# design.net
KiCad netlist of a schematic drawn in Altium Designer
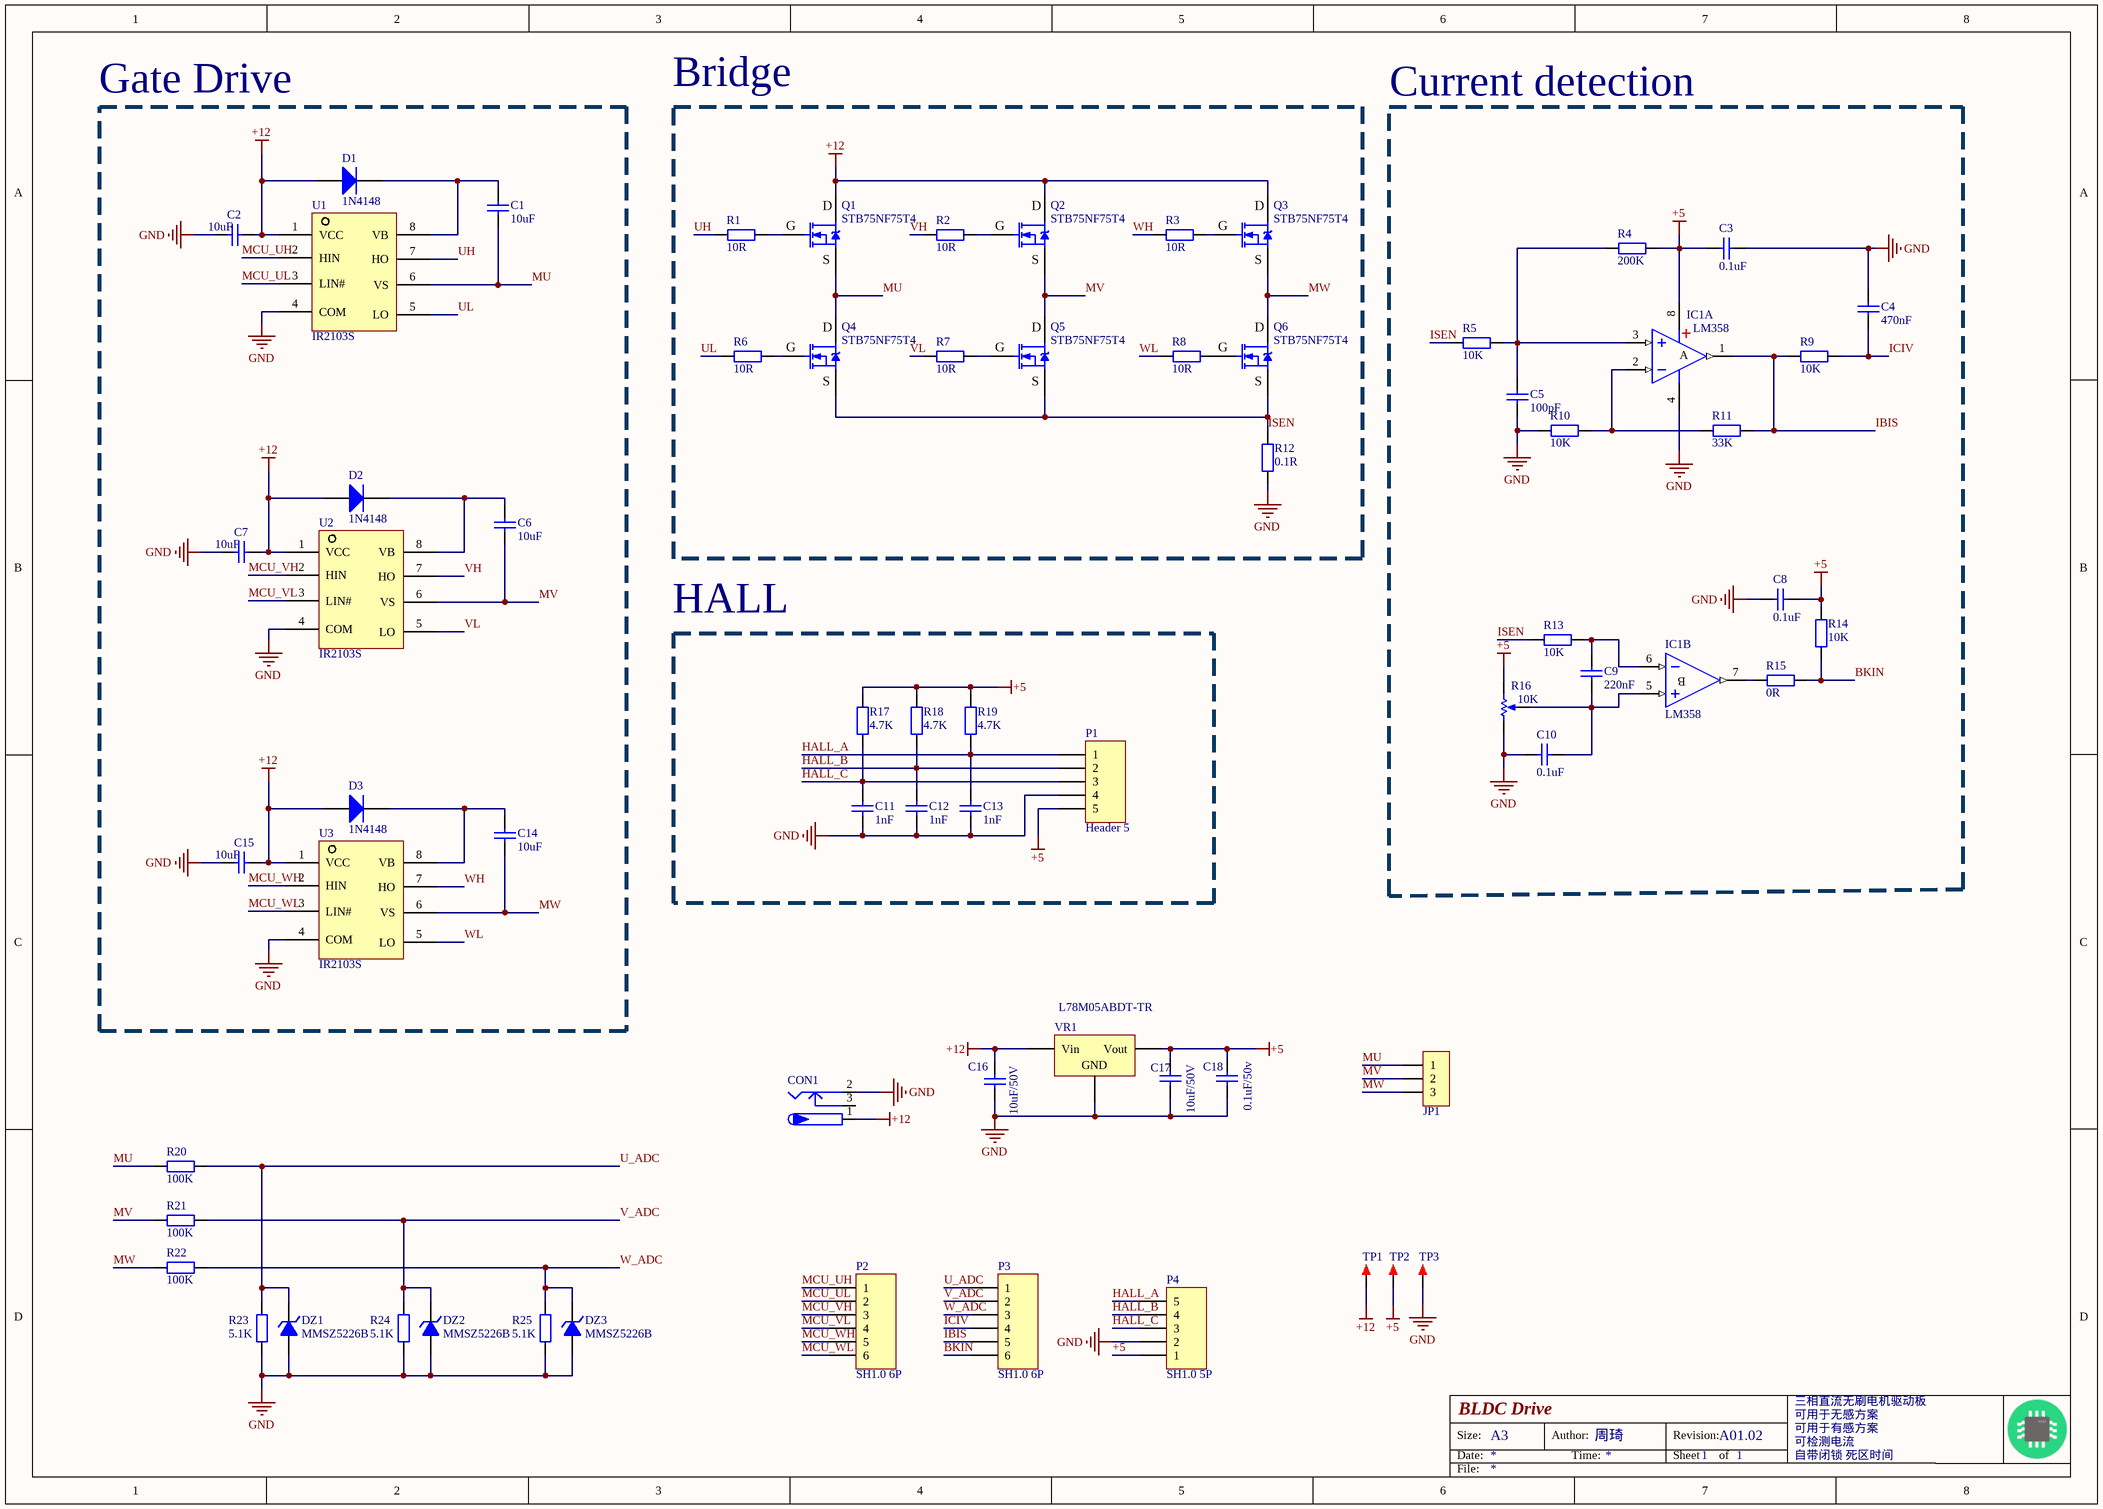
[diagram p0: 原理图.SchDoc]

(export (version "E")
  (design (tool "Eeschema 10.0.6"))
  (components
    (comp (ref "C1")
      (value "10uF")
      (footprint "C0603_L")
      (description "贴片电容")
      (libsource (lib "0.1 - 电阻-电容-电感-磁珠-电位器") (part "C"))
    )
    (comp (ref "C2")
      (value "10uF")
      (footprint "C0603_L")
      (description "贴片电容")
      (libsource (lib "0.1 - 电阻-电容-电感-磁珠-电位器") (part "C"))
    )
    (comp (ref "C3")
      (value "0.1uF")
      (footprint "C0603_L")
      (description "贴片电容")
      (libsource (lib "0.1 - 电阻-电容-电感-磁珠-电位器") (part "C"))
    )
    (comp (ref "C4")
      (value "470nF")
      (footprint "C0603_L")
      (description "贴片电容")
      (libsource (lib "0.1 - 电阻-电容-电感-磁珠-电位器") (part "C"))
    )
    (comp (ref "C5")
      (value "100pF")
      (footprint "C0603_L")
      (description "贴片电容")
      (libsource (lib "0.1 - 电阻-电容-电感-磁珠-电位器") (part "C"))
    )
    (comp (ref "C6")
      (value "10uF")
      (footprint "C0603_L")
      (description "贴片电容")
      (libsource (lib "0.1 - 电阻-电容-电感-磁珠-电位器") (part "C"))
    )
    (comp (ref "C7")
      (value "10uF")
      (footprint "C0603_L")
      (description "贴片电容")
      (libsource (lib "0.1 - 电阻-电容-电感-磁珠-电位器") (part "C"))
    )
    (comp (ref "C8")
      (value "0.1uF")
      (footprint "C0603_L")
      (description "贴片电容")
      (libsource (lib "0.1 - 电阻-电容-电感-磁珠-电位器") (part "C"))
    )
    (comp (ref "C9")
      (value "220nF")
      (footprint "C0603_L")
      (description "贴片电容")
      (libsource (lib "0.1 - 电阻-电容-电感-磁珠-电位器") (part "C"))
    )
    (comp (ref "C10")
      (value "0.1uF")
      (footprint "C0603_L")
      (description "贴片电容")
      (libsource (lib "0.1 - 电阻-电容-电感-磁珠-电位器") (part "C"))
    )
    (comp (ref "C11")
      (value "1nF")
      (footprint "C0603_L")
      (description "贴片电容")
      (libsource (lib "0.1 - 电阻-电容-电感-磁珠-电位器") (part "C"))
    )
    (comp (ref "C12")
      (value "1nF")
      (footprint "C0603_L")
      (description "贴片电容")
      (libsource (lib "0.1 - 电阻-电容-电感-磁珠-电位器") (part "C"))
    )
    (comp (ref "C13")
      (value "1nF")
      (footprint "C0603_L")
      (description "贴片电容")
      (libsource (lib "0.1 - 电阻-电容-电感-磁珠-电位器") (part "C"))
    )
    (comp (ref "C14")
      (value "10uF")
      (footprint "C0603_L")
      (description "贴片电容")
      (libsource (lib "0.1 - 电阻-电容-电感-磁珠-电位器") (part "C"))
    )
    (comp (ref "C15")
      (value "10uF")
      (footprint "C0603_L")
      (description "贴片电容")
      (libsource (lib "0.1 - 电阻-电容-电感-磁珠-电位器") (part "C"))
    )
    (comp (ref "C16")
      (value "10uF/50V")
      (footprint "C1206_L")
      (description "C89632")
      (libsource (lib "Miscellaneous Devices") (part "Cap"))
    )
    (comp (ref "C17")
      (value "10uF/50V")
      (footprint "C1206_L")
      (description "C89632")
      (libsource (lib "Miscellaneous Devices") (part "Cap"))
    )
    (comp (ref "C18")
      (value "0.1uF/50v")
      (footprint "C0603_L")
      (libsource (lib "Miscellaneous Devices") (part "Cap"))
    )
    (comp (ref "CON1")
      (value "3.5*1.3")
      (footprint "DC-005")
      (description "低压电源接口")
      (libsource (lib "0.8 - 以太网-音频-Type-C USB插座") (part "P-DC"))
    )
    (comp (ref "D1")
      (value "1N4148")
      (footprint "SOD-123")
      (description "二极管")
      (libsource (lib "Miscellaneous Devices LC") (part "SOD-323 1N4148WS T4"))
    )
    (comp (ref "D2")
      (value "1N4148")
      (footprint "SOD-123")
      (description "二极管")
      (libsource (lib "Miscellaneous Devices LC") (part "SOD-323 1N4148WS T4"))
    )
    (comp (ref "D3")
      (value "1N4148")
      (footprint "SOD-123")
      (description "二极管")
      (libsource (lib "Miscellaneous Devices LC") (part "SOD-323 1N4148WS T4"))
    )
    (comp (ref "DZ1")
      (value "MMSZ5226B")
      (footprint "SOD-123")
      (description "3V/0.5W稳压管")
      (libsource (lib "0.2 - 二极管-TVS-ESD-整流桥") (part "1N4619"))
    )
    (comp (ref "DZ2")
      (value "MMSZ5226B")
      (footprint "SOD-123")
      (description "3V/0.5W稳压管")
      (libsource (lib "0.2 - 二极管-TVS-ESD-整流桥") (part "1N4619"))
    )
    (comp (ref "DZ3")
      (value "MMSZ5226B")
      (footprint "SOD-123")
      (description "3V/0.5W稳压管")
      (libsource (lib "0.2 - 二极管-TVS-ESD-整流桥") (part "1N4619"))
    )
    (comp (ref "IC1")
      (value "LM358")
      (footprint "SOP8_N")
      (description "双路运放")
      (libsource (lib "1.0 - 常见芯片") (part "LM358"))
    )
    (comp (ref "JP1")
      (value "HDR-1X3")
      (footprint "KF350-3P")
      (description "3P接插件")
      (fields (field (name "版权归属") "源创客"))
      (libsource (lib "接插件") (part "Header 3"))
    )
    (comp (ref "P1")
      (value "Header 5")
      (footprint "SH 1.0-LS-5P")
      (description "Header, 5-Pin")
      (fields (field (name "PUBLISHER") "Altium Limited"))
      (libsource (lib "") (part "Header 5_1"))
    )
    (comp (ref "P2")
      (value "SH1.0 6P")
      (footprint "SH 1.0-WS-6P")
      (description "Header, 6-Pin")
      (fields (field (name "PUBLISHER") "Altium Limited"))
      (libsource (lib "Miscellaneous Connectors") (part "Header 6"))
    )
    (comp (ref "P3")
      (value "SH1.0 6P")
      (footprint "SH 1.0-WS-6P")
      (description "Header, 6-Pin")
      (fields (field (name "PUBLISHER") "Altium Limited"))
      (libsource (lib "Miscellaneous Connectors") (part "Header 6"))
    )
    (comp (ref "P4")
      (value "SH1.0 5P")
      (footprint "SH 1.0-LS-5P")
      (description "Header, 5-Pin")
      (fields (field (name "PUBLISHER") "Altium Limited"))
      (libsource (lib "Miscellaneous Connectors") (part "Header 5"))
    )
    (comp (ref "Q1")
      (value "STB75NF75T4")
      (footprint "TO252")
      (description "N沟道 55V/17A")
      (libsource (lib "0.4 - 三极管-场效应管-可控硅") (part "IRFR024NTRPBF"))
    )
    (comp (ref "Q2")
      (value "STB75NF75T4")
      (footprint "TO252")
      (description "N沟道 55V/17A")
      (libsource (lib "0.4 - 三极管-场效应管-可控硅") (part "IRFR024NTRPBF"))
    )
    (comp (ref "Q3")
      (value "STB75NF75T4")
      (footprint "TO252")
      (description "N沟道 55V/17A")
      (libsource (lib "0.4 - 三极管-场效应管-可控硅") (part "IRFR024NTRPBF"))
    )
    (comp (ref "Q4")
      (value "STB75NF75T4")
      (footprint "TO252")
      (description "N沟道 55V/17A")
      (libsource (lib "0.4 - 三极管-场效应管-可控硅") (part "IRFR024NTRPBF"))
    )
    (comp (ref "Q5")
      (value "STB75NF75T4")
      (footprint "TO252")
      (description "N沟道 55V/17A")
      (libsource (lib "0.4 - 三极管-场效应管-可控硅") (part "IRFR024NTRPBF"))
    )
    (comp (ref "Q6")
      (value "STB75NF75T4")
      (footprint "TO252")
      (description "N沟道 55V/17A")
      (libsource (lib "0.4 - 三极管-场效应管-可控硅") (part "IRFR024NTRPBF"))
    )
    (comp (ref "R1")
      (value "10R")
      (footprint "R0603_L")
      (description "贴片电阻")
      (libsource (lib "0.1 - 电阻-电容-电感-磁珠-电位器") (part "R"))
    )
    (comp (ref "R2")
      (value "10R")
      (footprint "R0603_L")
      (description "贴片电阻")
      (libsource (lib "0.1 - 电阻-电容-电感-磁珠-电位器") (part "R"))
    )
    (comp (ref "R3")
      (value "10R")
      (footprint "R0603_L")
      (description "贴片电阻")
      (libsource (lib "0.1 - 电阻-电容-电感-磁珠-电位器") (part "R"))
    )
    (comp (ref "R4")
      (value "200K")
      (footprint "R0603_L")
      (description "贴片电阻")
      (libsource (lib "0.1 - 电阻-电容-电感-磁珠-电位器") (part "R"))
    )
    (comp (ref "R5")
      (value "10K")
      (footprint "R0603_L")
      (description "贴片电阻")
      (libsource (lib "0.1 - 电阻-电容-电感-磁珠-电位器") (part "R"))
    )
    (comp (ref "R6")
      (value "10R")
      (footprint "R0603_L")
      (description "贴片电阻")
      (libsource (lib "0.1 - 电阻-电容-电感-磁珠-电位器") (part "R"))
    )
    (comp (ref "R7")
      (value "10R")
      (footprint "R0603_L")
      (description "贴片电阻")
      (libsource (lib "0.1 - 电阻-电容-电感-磁珠-电位器") (part "R"))
    )
    (comp (ref "R8")
      (value "10R")
      (footprint "R0603_L")
      (description "贴片电阻")
      (libsource (lib "0.1 - 电阻-电容-电感-磁珠-电位器") (part "R"))
    )
    (comp (ref "R9")
      (value "10K")
      (footprint "R0603_L")
      (description "贴片电阻")
      (libsource (lib "0.1 - 电阻-电容-电感-磁珠-电位器") (part "R"))
    )
    (comp (ref "R10")
      (value "10K")
      (footprint "R0603_L")
      (description "贴片电阻")
      (libsource (lib "0.1 - 电阻-电容-电感-磁珠-电位器") (part "R"))
    )
    (comp (ref "R11")
      (value "33K")
      (footprint "R0603_L")
      (description "贴片电阻")
      (libsource (lib "0.1 - 电阻-电容-电感-磁珠-电位器") (part "R"))
    )
    (comp (ref "R12")
      (value "0.1R")
      (footprint "R2512_M")
      (description "贴片电阻")
      (libsource (lib "0.1 - 电阻-电容-电感-磁珠-电位器") (part "R"))
    )
    (comp (ref "R13")
      (value "10K")
      (footprint "R0603_L")
      (description "贴片电阻")
      (libsource (lib "0.1 - 电阻-电容-电感-磁珠-电位器") (part "R"))
    )
    (comp (ref "R14")
      (value "10K")
      (footprint "R0603_L")
      (description "贴片电阻")
      (libsource (lib "0.1 - 电阻-电容-电感-磁珠-电位器") (part "R"))
    )
    (comp (ref "R15")
      (value "0R")
      (footprint "R0603_L")
      (description "贴片电阻")
      (libsource (lib "0.1 - 电阻-电容-电感-磁珠-电位器") (part "R"))
    )
    (comp (ref "R16")
      (value "10K")
      (footprint "3303W")
      (description "Potentiometer")
      (fields (field (name "Comment") "RPot") (field (name "PUBLISHER") "Altium Limited"))
      (libsource (lib "Miscellaneous Devices") (part "RPot"))
    )
    (comp (ref "R17")
      (value "4.7K")
      (footprint "R0603_L")
      (description "贴片电阻")
      (libsource (lib "0.1 - 电阻-电容-电感-磁珠-电位器") (part "R"))
    )
    (comp (ref "R18")
      (value "4.7K")
      (footprint "R0603_L")
      (description "贴片电阻")
      (libsource (lib "0.1 - 电阻-电容-电感-磁珠-电位器") (part "R"))
    )
    (comp (ref "R19")
      (value "4.7K")
      (footprint "R0603_L")
      (description "贴片电阻")
      (libsource (lib "0.1 - 电阻-电容-电感-磁珠-电位器") (part "R"))
    )
    (comp (ref "R20")
      (value "100K")
      (footprint "R1206_L")
      (description "贴片电阻")
      (libsource (lib "0.1 - 电阻-电容-电感-磁珠-电位器") (part "R"))
    )
    (comp (ref "R21")
      (value "100K")
      (footprint "R1206_L")
      (description "贴片电阻")
      (libsource (lib "0.1 - 电阻-电容-电感-磁珠-电位器") (part "R"))
    )
    (comp (ref "R22")
      (value "100K")
      (footprint "R1206_L")
      (description "贴片电阻")
      (libsource (lib "0.1 - 电阻-电容-电感-磁珠-电位器") (part "R"))
    )
    (comp (ref "R23")
      (value "5.1K")
      (footprint "R0805_L")
      (description "贴片电阻")
      (libsource (lib "0.1 - 电阻-电容-电感-磁珠-电位器") (part "R"))
    )
    (comp (ref "R24")
      (value "5.1K")
      (footprint "R0805_L")
      (description "贴片电阻")
      (libsource (lib "0.1 - 电阻-电容-电感-磁珠-电位器") (part "R"))
    )
    (comp (ref "R25")
      (value "5.1K")
      (footprint "R0805_L")
      (description "贴片电阻")
      (libsource (lib "0.1 - 电阻-电容-电感-磁珠-电位器") (part "R"))
    )
    (comp (ref "TP1")
      (value "TEST")
      (footprint "TEST 1.6")
      (description "测试点")
      (libsource (lib "0.7 - 常用按键-开关-蜂鸣器-电池-测试点") (part "TEST"))
    )
    (comp (ref "TP2")
      (value "TEST")
      (footprint "TEST 1.6")
      (description "测试点")
      (libsource (lib "0.7 - 常用按键-开关-蜂鸣器-电池-测试点") (part "TEST"))
    )
    (comp (ref "TP3")
      (value "TEST")
      (footprint "TEST 1.6")
      (description "测试点")
      (libsource (lib "0.7 - 常用按键-开关-蜂鸣器-电池-测试点") (part "TEST"))
    )
    (comp (ref "U1")
      (value "IR2103S")
      (footprint "SOP8")
      (description "栅极驱动，SOP-8")
      (libsource (lib "Schlib1") (part "IR2103S"))
    )
    (comp (ref "U2")
      (value "IR2103S")
      (footprint "SOP8")
      (description "栅极驱动，SOP-8")
      (libsource (lib "Schlib1") (part "IR2103S"))
    )
    (comp (ref "U3")
      (value "IR2103S")
      (footprint "SOP8")
      (description "栅极驱动，SOP-8")
      (libsource (lib "Schlib1") (part "IR2103S"))
    )
    (comp (ref "VR1")
      (value "L78M05ABDT-TR")
      (footprint "TO-252")
      (description "低压差线性稳压(LDO)")
      (libsource (lib "LDO") (part "TO-252-2 L78M05ABDT-TR"))
    )
  )
  (nets
    (net (code "1") (name "+5") (class "Default")
      (node (ref "C17") (pin "2") (pinfunction "2_2") (pintype "passive"))
      (node (ref "C18") (pin "2") (pinfunction "2_2") (pintype "passive"))
      (node (ref "C3") (pin "1") (pinfunction "1_1") (pintype "passive"))
      (node (ref "C8") (pin "1") (pinfunction "1_1") (pintype "passive"))
      (node (ref "IC1") (pin "8") (pinfunction "V+_8") (pintype "power_in"))
      (node (ref "P1") (pin "5") (pinfunction "5_5") (pintype "passive"))
      (node (ref "P4") (pin "1") (pinfunction "1_1") (pintype "passive"))
      (node (ref "R14") (pin "1") (pinfunction "1_1") (pintype "passive"))
      (node (ref "R16") (pin "2") (pinfunction "BOT_2") (pintype "passive"))
      (node (ref "R17") (pin "2") (pinfunction "2_2") (pintype "passive"))
      (node (ref "R18") (pin "2") (pinfunction "2_2") (pintype "passive"))
      (node (ref "R19") (pin "2") (pinfunction "2_2") (pintype "passive"))
      (node (ref "R4") (pin "1") (pinfunction "1_1") (pintype "passive"))
      (node (ref "TP2") (pin "1") (pinfunction "1_1") (pintype "passive"))
      (node (ref "VR1") (pin "3") (pinfunction "Vout_3") (pintype "passive"))
    )
    (net (code "2") (name "+12") (class "Default")
      (node (ref "C15") (pin "2") (pinfunction "2_2") (pintype "passive"))
      (node (ref "C16") (pin "2") (pinfunction "2_2") (pintype "passive"))
      (node (ref "C2") (pin "2") (pinfunction "2_2") (pintype "passive"))
      (node (ref "C7") (pin "2") (pinfunction "2_2") (pintype "passive"))
      (node (ref "CON1") (pin "1") (pintype "power_in"))
      (node (ref "D1") (pin "1") (pinfunction "A_1") (pintype "passive"))
      (node (ref "D2") (pin "1") (pinfunction "A_1") (pintype "passive"))
      (node (ref "D3") (pin "1") (pinfunction "A_1") (pintype "passive"))
      (node (ref "Q1") (pin "2") (pinfunction "D_2") (pintype "passive"))
      (node (ref "Q2") (pin "2") (pinfunction "D_2") (pintype "passive"))
      (node (ref "Q3") (pin "2") (pinfunction "D_2") (pintype "passive"))
      (node (ref "TP1") (pin "1") (pinfunction "1_1") (pintype "passive"))
      (node (ref "U1") (pin "1") (pinfunction "VCC_1") (pintype "passive"))
      (node (ref "U2") (pin "1") (pinfunction "VCC_1") (pintype "passive"))
      (node (ref "U3") (pin "1") (pinfunction "VCC_1") (pintype "passive"))
      (node (ref "VR1") (pin "1") (pinfunction "Vin_1") (pintype "passive"))
    )
    (net (code "3") (name "/BKIN") (class "Default")
      (node (ref "P3") (pin "6") (pinfunction "6_6") (pintype "passive"))
      (node (ref "R14") (pin "2") (pinfunction "2_2") (pintype "passive"))
      (node (ref "R15") (pin "1") (pinfunction "1_1") (pintype "passive"))
    )
    (net (code "4") (name "/HALL_A") (class "Default")
      (node (ref "C13") (pin "2") (pinfunction "2_2") (pintype "passive"))
      (node (ref "P1") (pin "1") (pinfunction "1_1") (pintype "passive"))
      (node (ref "P4") (pin "5") (pinfunction "5_5") (pintype "passive"))
      (node (ref "R19") (pin "1") (pinfunction "1_1") (pintype "passive"))
    )
    (net (code "5") (name "/HALL_B") (class "Default")
      (node (ref "C12") (pin "2") (pinfunction "2_2") (pintype "passive"))
      (node (ref "P1") (pin "2") (pinfunction "2_2") (pintype "passive"))
      (node (ref "P4") (pin "4") (pinfunction "4_4") (pintype "passive"))
      (node (ref "R18") (pin "1") (pinfunction "1_1") (pintype "passive"))
    )
    (net (code "6") (name "/HALL_C") (class "Default")
      (node (ref "C11") (pin "2") (pinfunction "2_2") (pintype "passive"))
      (node (ref "P1") (pin "3") (pinfunction "3_3") (pintype "passive"))
      (node (ref "P4") (pin "3") (pinfunction "3_3") (pintype "passive"))
      (node (ref "R17") (pin "1") (pinfunction "1_1") (pintype "passive"))
    )
    (net (code "7") (name "/IBIS") (class "Default")
      (node (ref "IC1") (pin "1") (pinfunction "OUT_1") (pintype "output"))
      (node (ref "P3") (pin "5") (pinfunction "5_5") (pintype "passive"))
      (node (ref "R11") (pin "1") (pinfunction "1_1") (pintype "passive"))
      (node (ref "R9") (pin "2") (pinfunction "2_2") (pintype "passive"))
    )
    (net (code "8") (name "/ICIV") (class "Default")
      (node (ref "C4") (pin "2") (pinfunction "2_2") (pintype "passive"))
      (node (ref "P3") (pin "4") (pinfunction "4_4") (pintype "passive"))
      (node (ref "R9") (pin "1") (pinfunction "1_1") (pintype "passive"))
    )
    (net (code "9") (name "/ISEN") (class "Default")
      (node (ref "Q4") (pin "3") (pinfunction "S_3") (pintype "passive"))
      (node (ref "Q5") (pin "3") (pinfunction "S_3") (pintype "passive"))
      (node (ref "Q6") (pin "3") (pinfunction "S_3") (pintype "passive"))
      (node (ref "R12") (pin "2") (pinfunction "2_2") (pintype "passive"))
      (node (ref "R13") (pin "2") (pinfunction "2_2") (pintype "passive"))
      (node (ref "R5") (pin "2") (pinfunction "2_2") (pintype "passive"))
    )
    (net (code "10") (name "/MCU_UH") (class "Default")
      (node (ref "P2") (pin "1") (pinfunction "1_1") (pintype "passive"))
      (node (ref "U1") (pin "2") (pinfunction "HIN_2") (pintype "passive"))
    )
    (net (code "11") (name "/MCU_UL") (class "Default")
      (node (ref "P2") (pin "2") (pinfunction "2_2") (pintype "passive"))
      (node (ref "U1") (pin "3") (pinfunction "LIN#_3") (pintype "passive"))
    )
    (net (code "12") (name "/MCU_VH") (class "Default")
      (node (ref "P2") (pin "3") (pinfunction "3_3") (pintype "passive"))
      (node (ref "U2") (pin "2") (pinfunction "HIN_2") (pintype "passive"))
    )
    (net (code "13") (name "/MCU_VL") (class "Default")
      (node (ref "P2") (pin "4") (pinfunction "4_4") (pintype "passive"))
      (node (ref "U2") (pin "3") (pinfunction "LIN#_3") (pintype "passive"))
    )
    (net (code "14") (name "/MCU_WH") (class "Default")
      (node (ref "P2") (pin "5") (pinfunction "5_5") (pintype "passive"))
      (node (ref "U3") (pin "2") (pinfunction "HIN_2") (pintype "passive"))
    )
    (net (code "15") (name "/MCU_WL") (class "Default")
      (node (ref "P2") (pin "6") (pinfunction "6_6") (pintype "passive"))
      (node (ref "U3") (pin "3") (pinfunction "LIN#_3") (pintype "passive"))
    )
    (net (code "16") (name "/MU") (class "Default")
      (node (ref "C1") (pin "1") (pinfunction "1_1") (pintype "passive"))
      (node (ref "JP1") (pin "1") (pinfunction "1_1") (pintype "passive"))
      (node (ref "Q1") (pin "3") (pinfunction "S_3") (pintype "passive"))
      (node (ref "Q4") (pin "2") (pinfunction "D_2") (pintype "passive"))
      (node (ref "R20") (pin "1") (pinfunction "1_1") (pintype "passive"))
      (node (ref "U1") (pin "6") (pinfunction "VS_6") (pintype "passive"))
    )
    (net (code "17") (name "/MV") (class "Default")
      (node (ref "C6") (pin "1") (pinfunction "1_1") (pintype "passive"))
      (node (ref "JP1") (pin "2") (pinfunction "2_2") (pintype "passive"))
      (node (ref "Q2") (pin "3") (pinfunction "S_3") (pintype "passive"))
      (node (ref "Q5") (pin "2") (pinfunction "D_2") (pintype "passive"))
      (node (ref "R21") (pin "1") (pinfunction "1_1") (pintype "passive"))
      (node (ref "U2") (pin "6") (pinfunction "VS_6") (pintype "passive"))
    )
    (net (code "18") (name "/MW") (class "Default")
      (node (ref "C14") (pin "1") (pinfunction "1_1") (pintype "passive"))
      (node (ref "JP1") (pin "3") (pinfunction "3_3") (pintype "passive"))
      (node (ref "Q3") (pin "3") (pinfunction "S_3") (pintype "passive"))
      (node (ref "Q6") (pin "2") (pinfunction "D_2") (pintype "passive"))
      (node (ref "R22") (pin "1") (pinfunction "1_1") (pintype "passive"))
      (node (ref "U3") (pin "6") (pinfunction "VS_6") (pintype "passive"))
    )
    (net (code "19") (name "/UH") (class "Default")
      (node (ref "R1") (pin "1") (pinfunction "1_1") (pintype "passive"))
      (node (ref "U1") (pin "7") (pinfunction "HO_7") (pintype "passive"))
    )
    (net (code "20") (name "/UL") (class "Default")
      (node (ref "R6") (pin "1") (pinfunction "1_1") (pintype "passive"))
      (node (ref "U1") (pin "5") (pinfunction "LO_5") (pintype "passive"))
    )
    (net (code "21") (name "/U_ADC") (class "Default")
      (node (ref "DZ1") (pin "2") (pinfunction "K_2") (pintype "passive"))
      (node (ref "P3") (pin "1") (pinfunction "1_1") (pintype "passive"))
      (node (ref "R20") (pin "2") (pinfunction "2_2") (pintype "passive"))
      (node (ref "R23") (pin "2") (pinfunction "2_2") (pintype "passive"))
    )
    (net (code "22") (name "/VH") (class "Default")
      (node (ref "R2") (pin "1") (pinfunction "1_1") (pintype "passive"))
      (node (ref "U2") (pin "7") (pinfunction "HO_7") (pintype "passive"))
    )
    (net (code "23") (name "/VL") (class "Default")
      (node (ref "R7") (pin "1") (pinfunction "1_1") (pintype "passive"))
      (node (ref "U2") (pin "5") (pinfunction "LO_5") (pintype "passive"))
    )
    (net (code "24") (name "/V_ADC") (class "Default")
      (node (ref "DZ2") (pin "2") (pinfunction "K_2") (pintype "passive"))
      (node (ref "P3") (pin "2") (pinfunction "2_2") (pintype "passive"))
      (node (ref "R21") (pin "2") (pinfunction "2_2") (pintype "passive"))
      (node (ref "R24") (pin "2") (pinfunction "2_2") (pintype "passive"))
    )
    (net (code "25") (name "/WH") (class "Default")
      (node (ref "R3") (pin "1") (pinfunction "1_1") (pintype "passive"))
      (node (ref "U3") (pin "7") (pinfunction "HO_7") (pintype "passive"))
    )
    (net (code "26") (name "/WL") (class "Default")
      (node (ref "R8") (pin "1") (pinfunction "1_1") (pintype "passive"))
      (node (ref "U3") (pin "5") (pinfunction "LO_5") (pintype "passive"))
    )
    (net (code "27") (name "/W_ADC") (class "Default")
      (node (ref "DZ3") (pin "2") (pinfunction "K_2") (pintype "passive"))
      (node (ref "P3") (pin "3") (pinfunction "3_3") (pintype "passive"))
      (node (ref "R22") (pin "2") (pinfunction "2_2") (pintype "passive"))
      (node (ref "R25") (pin "2") (pinfunction "2_2") (pintype "passive"))
    )
    (net (code "28") (name "GND") (class "Default")
      (node (ref "C10") (pin "2") (pinfunction "2_2") (pintype "passive"))
      (node (ref "C11") (pin "1") (pinfunction "1_1") (pintype "passive"))
      (node (ref "C12") (pin "1") (pinfunction "1_1") (pintype "passive"))
      (node (ref "C13") (pin "1") (pinfunction "1_1") (pintype "passive"))
      (node (ref "C15") (pin "1") (pinfunction "1_1") (pintype "passive"))
      (node (ref "C16") (pin "1") (pinfunction "1_1") (pintype "passive"))
      (node (ref "C17") (pin "1") (pinfunction "1_1") (pintype "passive"))
      (node (ref "C18") (pin "1") (pinfunction "1_1") (pintype "passive"))
      (node (ref "C2") (pin "1") (pinfunction "1_1") (pintype "passive"))
      (node (ref "C3") (pin "2") (pinfunction "2_2") (pintype "passive"))
      (node (ref "C4") (pin "1") (pinfunction "1_1") (pintype "passive"))
      (node (ref "C5") (pin "2") (pinfunction "2_2") (pintype "passive"))
      (node (ref "C7") (pin "1") (pinfunction "1_1") (pintype "passive"))
      (node (ref "C8") (pin "2") (pinfunction "2_2") (pintype "passive"))
      (node (ref "CON1") (pin "2") (pintype "power_in"))
      (node (ref "DZ1") (pin "1") (pinfunction "A_1") (pintype "passive"))
      (node (ref "DZ2") (pin "1") (pinfunction "A_1") (pintype "passive"))
      (node (ref "DZ3") (pin "1") (pinfunction "A_1") (pintype "passive"))
      (node (ref "IC1") (pin "4") (pinfunction "V-_4") (pintype "power_in"))
      (node (ref "P1") (pin "4") (pinfunction "4_4") (pintype "passive"))
      (node (ref "P4") (pin "2") (pinfunction "2_2") (pintype "passive"))
      (node (ref "R10") (pin "2") (pinfunction "2_2") (pintype "passive"))
      (node (ref "R12") (pin "1") (pinfunction "1_1") (pintype "passive"))
      (node (ref "R16") (pin "1") (pinfunction "TOP_1") (pintype "passive"))
      (node (ref "R23") (pin "1") (pinfunction "1_1") (pintype "passive"))
      (node (ref "R24") (pin "1") (pinfunction "1_1") (pintype "passive"))
      (node (ref "R25") (pin "1") (pinfunction "1_1") (pintype "passive"))
      (node (ref "TP3") (pin "1") (pinfunction "1_1") (pintype "passive"))
      (node (ref "U1") (pin "4") (pinfunction "COM_4") (pintype "passive"))
      (node (ref "U2") (pin "4") (pinfunction "COM_4") (pintype "passive"))
      (node (ref "U3") (pin "4") (pinfunction "COM_4") (pintype "passive"))
      (node (ref "VR1") (pin "2") (pinfunction "GND_2") (pintype "passive"))
    )
    (net (code "29") (name "Net-(D1-K)") (class "Default")
      (node (ref "C1") (pin "2") (pinfunction "2_2") (pintype "passive"))
      (node (ref "D1") (pin "2") (pinfunction "K_2") (pintype "passive"))
      (node (ref "U1") (pin "8") (pinfunction "VB_8") (pintype "passive"))
    )
    (net (code "30") (name "Net-(D2-K)") (class "Default")
      (node (ref "C6") (pin "2") (pinfunction "2_2") (pintype "passive"))
      (node (ref "D2") (pin "2") (pinfunction "K_2") (pintype "passive"))
      (node (ref "U2") (pin "8") (pinfunction "VB_8") (pintype "passive"))
    )
    (net (code "31") (name "Net-(D3-K)") (class "Default")
      (node (ref "C14") (pin "2") (pinfunction "2_2") (pintype "passive"))
      (node (ref "D3") (pin "2") (pinfunction "K_2") (pintype "passive"))
      (node (ref "U3") (pin "8") (pinfunction "VB_8") (pintype "passive"))
    )
    (net (code "32") (name "Net-(IC1A-IN+)") (class "Default")
      (node (ref "C5") (pin "1") (pinfunction "1_1") (pintype "passive"))
      (node (ref "IC1") (pin "3") (pinfunction "IN+_3") (pintype "input"))
      (node (ref "R4") (pin "2") (pinfunction "2_2") (pintype "passive"))
      (node (ref "R5") (pin "1") (pinfunction "1_1") (pintype "passive"))
    )
    (net (code "33") (name "Net-(IC1A-IN-)") (class "Default")
      (node (ref "IC1") (pin "2") (pinfunction "IN-_2") (pintype "input"))
      (node (ref "R10") (pin "1") (pinfunction "1_1") (pintype "passive"))
      (node (ref "R11") (pin "2") (pinfunction "2_2") (pintype "passive"))
    )
    (net (code "34") (name "Net-(IC1B-IN+)") (class "Default")
      (node (ref "C10") (pin "1") (pinfunction "1_1") (pintype "passive"))
      (node (ref "C9") (pin "1") (pinfunction "1_1") (pintype "passive"))
      (node (ref "IC1") (pin "5") (pinfunction "IN+_5") (pintype "input"))
      (node (ref "R16") (pin "3") (pinfunction "TAP_3") (pintype "passive"))
    )
    (net (code "35") (name "Net-(IC1B-IN-)") (class "Default")
      (node (ref "C9") (pin "2") (pinfunction "2_2") (pintype "passive"))
      (node (ref "IC1") (pin "6") (pinfunction "IN-_6") (pintype "input"))
      (node (ref "R13") (pin "1") (pinfunction "1_1") (pintype "passive"))
    )
    (net (code "36") (name "Net-(IC1B-OUT)") (class "Default")
      (node (ref "IC1") (pin "7") (pinfunction "OUT_7") (pintype "output"))
      (node (ref "R15") (pin "2") (pinfunction "2_2") (pintype "passive"))
    )
    (net (code "37") (name "Net-(Q1-G)") (class "Default")
      (node (ref "Q1") (pin "1") (pinfunction "G_1") (pintype "passive"))
      (node (ref "R1") (pin "2") (pinfunction "2_2") (pintype "passive"))
    )
    (net (code "38") (name "Net-(Q2-G)") (class "Default")
      (node (ref "Q2") (pin "1") (pinfunction "G_1") (pintype "passive"))
      (node (ref "R2") (pin "2") (pinfunction "2_2") (pintype "passive"))
    )
    (net (code "39") (name "Net-(Q3-G)") (class "Default")
      (node (ref "Q3") (pin "1") (pinfunction "G_1") (pintype "passive"))
      (node (ref "R3") (pin "2") (pinfunction "2_2") (pintype "passive"))
    )
    (net (code "40") (name "Net-(Q4-G)") (class "Default")
      (node (ref "Q4") (pin "1") (pinfunction "G_1") (pintype "passive"))
      (node (ref "R6") (pin "2") (pinfunction "2_2") (pintype "passive"))
    )
    (net (code "41") (name "Net-(Q5-G)") (class "Default")
      (node (ref "Q5") (pin "1") (pinfunction "G_1") (pintype "passive"))
      (node (ref "R7") (pin "2") (pinfunction "2_2") (pintype "passive"))
    )
    (net (code "42") (name "Net-(Q6-G)") (class "Default")
      (node (ref "Q6") (pin "1") (pinfunction "G_1") (pintype "passive"))
      (node (ref "R8") (pin "2") (pinfunction "2_2") (pintype "passive"))
    )
    (net (code "43") (name "unconnected-(CON1-Pad3)") (class "Default")
      (node (ref "CON1") (pin "3") (pintype "power_in"))
    )
  )
)
